# digit_4.net
KiCad netlist of a schematic drawn in EAGLE
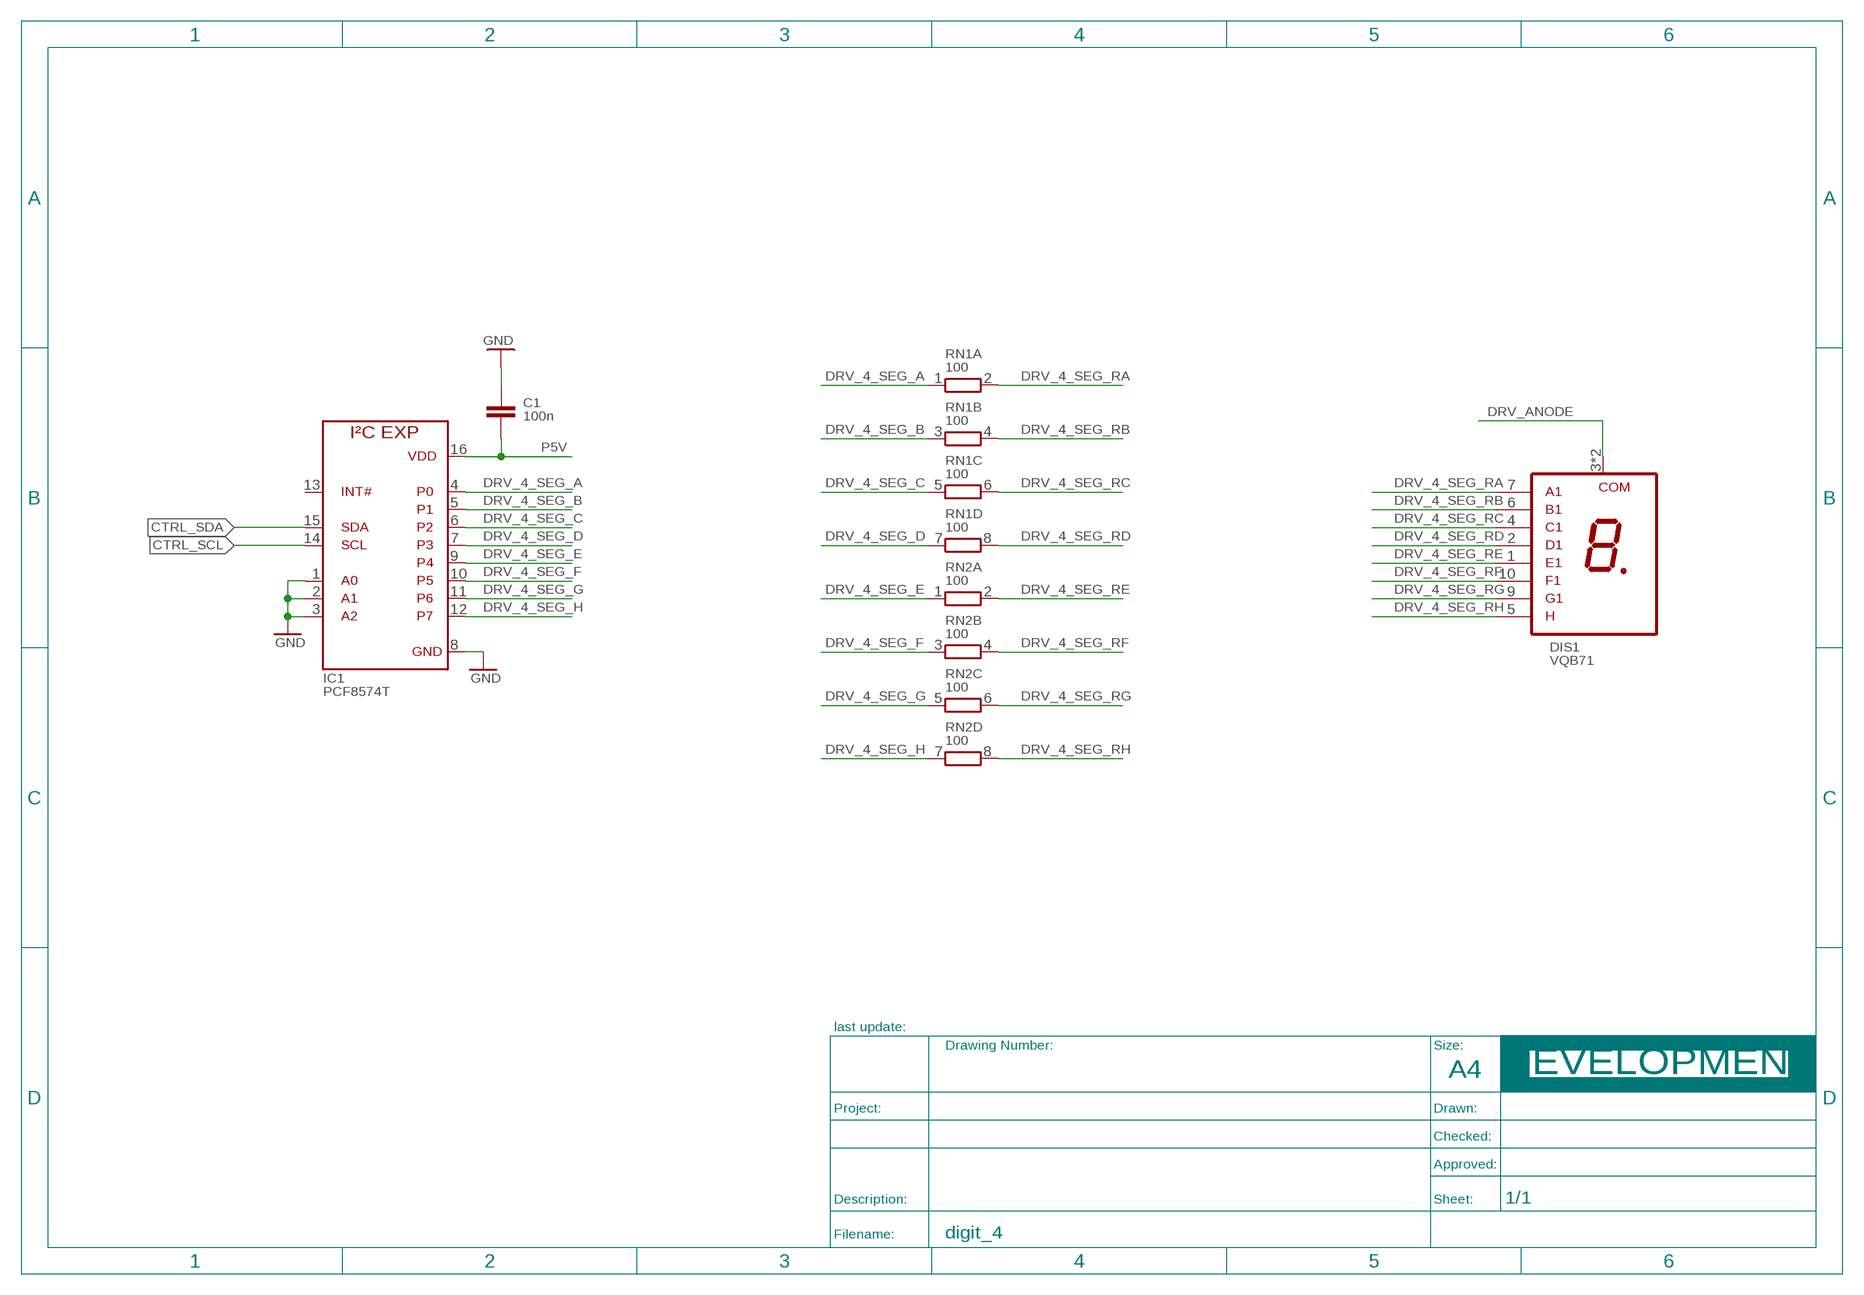
[diagram p0: schematic, sheet 1]

(export (version "E")
  (design (tool "Eeschema 10.0.6"))
  (components
    (comp (ref "C1")
      (value "100n")
      (footprint "eagle-import:S_0805")
      (fields (field (name "PART_CODE_BEL") "C_PAC_S_0805_VAL_100n"))
      (libsource (lib "eagle-import") (part "C_EU_S_0805"))
    )
    (comp (ref "DIS1")
      (value "VQB71")
      (footprint "eagle-import:T_VQB71")
      (libsource (lib "eagle-import") (part "VQB71"))
    )
    (comp (ref "IC1")
      (value "PCF8574T")
      (footprint "eagle-import:S_SOIC16")
      (libsource (lib "eagle-import") (part "PCF8574T"))
    )
    (comp (ref "RN1")
      (value "100")
      (footprint "eagle-import:T_SIL8")
      (fields (field (name "PART_CODE_BEL") "RN_PAC_T_SIL8_VAL_100"))
      (libsource (lib "eagle-import") (part "R_EU_ARRAY_4"))
    )
    (comp (ref "RN2")
      (value "100")
      (footprint "eagle-import:T_SIL8")
      (fields (field (name "PART_CODE_BEL") "RN_PAC_T_SIL8_VAL_100"))
      (libsource (lib "eagle-import") (part "R_EU_ARRAY_4"))
    )
  )
  (nets
    (net (code "1") (name "/DRV_4_SEG_A") (class "Default")
      (node (ref "IC1") (pin "4") (pinfunction "P0_4") (pintype "bidirectional"))
      (node (ref "RN1") (pin "1") (pinfunction "1_1") (pintype "passive"))
    )
    (net (code "2") (name "/DRV_4_SEG_B") (class "Default")
      (node (ref "IC1") (pin "5") (pinfunction "P1_5") (pintype "bidirectional"))
      (node (ref "RN1") (pin "3") (pinfunction "1_3") (pintype "passive"))
    )
    (net (code "3") (name "/DRV_4_SEG_C") (class "Default")
      (node (ref "IC1") (pin "6") (pinfunction "P2_6") (pintype "bidirectional"))
      (node (ref "RN1") (pin "5") (pinfunction "1_5") (pintype "passive"))
    )
    (net (code "4") (name "/DRV_4_SEG_D") (class "Default")
      (node (ref "IC1") (pin "7") (pinfunction "P3_7") (pintype "bidirectional"))
      (node (ref "RN1") (pin "7") (pinfunction "1_7") (pintype "passive"))
    )
    (net (code "5") (name "/DRV_4_SEG_E") (class "Default")
      (node (ref "IC1") (pin "9") (pinfunction "P4_9") (pintype "bidirectional"))
      (node (ref "RN2") (pin "1") (pinfunction "1_1") (pintype "passive"))
    )
    (net (code "6") (name "/DRV_4_SEG_F") (class "Default")
      (node (ref "IC1") (pin "10") (pinfunction "P5_10") (pintype "bidirectional"))
      (node (ref "RN2") (pin "3") (pinfunction "1_3") (pintype "passive"))
    )
    (net (code "7") (name "/DRV_4_SEG_G") (class "Default")
      (node (ref "IC1") (pin "11") (pinfunction "P6_11") (pintype "bidirectional"))
      (node (ref "RN2") (pin "5") (pinfunction "1_5") (pintype "passive"))
    )
    (net (code "8") (name "/DRV_4_SEG_H") (class "Default")
      (node (ref "IC1") (pin "12") (pinfunction "P7_12") (pintype "bidirectional"))
      (node (ref "RN2") (pin "7") (pinfunction "1_7") (pintype "passive"))
    )
    (net (code "9") (name "/DRV_4_SEG_RA") (class "Default")
      (node (ref "DIS1") (pin "7") (pinfunction "A1_7") (pintype "passive"))
      (node (ref "RN1") (pin "2") (pinfunction "2_2") (pintype "passive"))
    )
    (net (code "10") (name "/DRV_4_SEG_RB") (class "Default")
      (node (ref "DIS1") (pin "6") (pinfunction "B1_6") (pintype "passive"))
      (node (ref "RN1") (pin "4") (pinfunction "2_4") (pintype "passive"))
    )
    (net (code "11") (name "/DRV_4_SEG_RC") (class "Default")
      (node (ref "DIS1") (pin "4") (pinfunction "C1_4") (pintype "passive"))
      (node (ref "RN1") (pin "6") (pinfunction "2_6") (pintype "passive"))
    )
    (net (code "12") (name "/DRV_4_SEG_RD") (class "Default")
      (node (ref "DIS1") (pin "2") (pinfunction "D1_2") (pintype "passive"))
      (node (ref "RN1") (pin "8") (pinfunction "2_8") (pintype "passive"))
    )
    (net (code "13") (name "/DRV_4_SEG_RE") (class "Default")
      (node (ref "DIS1") (pin "1") (pinfunction "E1_1") (pintype "passive"))
      (node (ref "RN2") (pin "2") (pinfunction "2_2") (pintype "passive"))
    )
    (net (code "14") (name "/DRV_4_SEG_RF") (class "Default")
      (node (ref "DIS1") (pin "10") (pinfunction "F1_10") (pintype "passive"))
      (node (ref "RN2") (pin "4") (pinfunction "2_4") (pintype "passive"))
    )
    (net (code "15") (name "/DRV_4_SEG_RG") (class "Default")
      (node (ref "DIS1") (pin "9") (pinfunction "G1_9") (pintype "passive"))
      (node (ref "RN2") (pin "6") (pinfunction "2_6") (pintype "passive"))
    )
    (net (code "16") (name "/DRV_4_SEG_RH") (class "Default")
      (node (ref "DIS1") (pin "5") (pinfunction "DP1_5") (pintype "passive"))
      (node (ref "RN2") (pin "8") (pinfunction "2_8") (pintype "passive"))
    )
    (net (code "17") (name "/DRV_ANODE") (class "Default")
      (node (ref "DIS1") (pin "3") (pinfunction "COM1_3") (pintype "passive"))
      (node (ref "DIS1") (pin "8") (pinfunction "COM1_8") (pintype "passive"))
    )
    (net (code "18") (name "/P5V") (class "Default")
      (node (ref "C1") (pin "2") (pinfunction "2_2") (pintype "passive"))
      (node (ref "IC1") (pin "16") (pinfunction "VDD_16") (pintype "power_in"))
    )
    (net (code "19") (name "CTRL_SCL") (class "Default")
      (node (ref "IC1") (pin "14") (pinfunction "SCL_14") (pintype "input"))
    )
    (net (code "20") (name "CTRL_SDA") (class "Default")
      (node (ref "IC1") (pin "15") (pinfunction "SDA_15") (pintype "bidirectional"))
    )
    (net (code "21") (name "GND") (class "Default")
      (node (ref "C1") (pin "1") (pinfunction "1_1") (pintype "passive"))
      (node (ref "IC1") (pin "1") (pinfunction "A0_1") (pintype "input"))
      (node (ref "IC1") (pin "2") (pinfunction "A1_2") (pintype "input"))
      (node (ref "IC1") (pin "3") (pinfunction "A2_3") (pintype "input"))
      (node (ref "IC1") (pin "8") (pinfunction "GND_8") (pintype "power_in"))
    )
    (net (code "22") (name "unconnected-(IC1-~{INT}-Pad13)") (class "Default")
      (node (ref "IC1") (pin "13") (pinfunction "~{INT}_13") (pintype "output"))
    )
  )
)
